# JDM2_2-Voltage_JmpConf_VDDctrl_LED.net
KiCad netlist of a schematic drawn in EAGLE
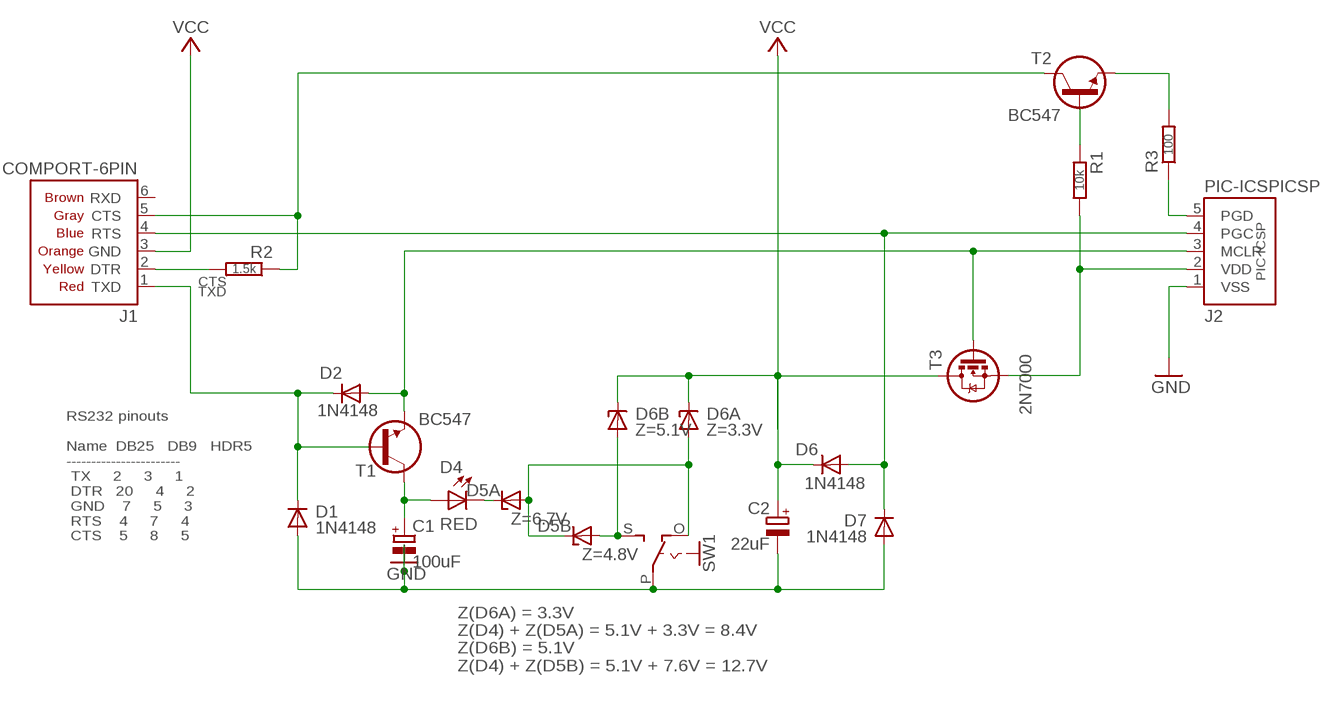
[diagram p0: schematic, sheet 1]

(export (version "E")
  (design (tool "Eeschema 10.0.6"))
  (components
    (comp (ref "C1")
      (value "100uF")
      (footprint "eagle-import:E2,5-5_V")
      (libsource (lib "eagle-import") (part "CPOLE2,5-5/V"))
    )
    (comp (ref "C2")
      (value "22uF")
      (footprint "eagle-import:E2.5-4_V")
      (libsource (lib "eagle-import") (part "CPOLE2,5-4/V"))
    )
    (comp (ref "D1")
      (value "1N4148")
      (footprint "eagle-import:DO34-5")
      (libsource (lib "eagle-import") (part "1N414834-5"))
    )
    (comp (ref "D2")
      (value "1N4148")
      (footprint "eagle-import:DO34-5")
      (libsource (lib "eagle-import") (part "1N414834-5"))
    )
    (comp (ref "D4")
      (value "RED")
      (footprint "eagle-import:LED3MM")
      (fields (field (name "MF") "VISHAY SEMICONDUCTOR"))
      (libsource (lib "eagle-import") (part "TLLR4400"))
    )
    (comp (ref "D5A")
      (value "Z=6.7V")
      (footprint "eagle-import:DO34Z7")
      (libsource (lib "eagle-import") (part "Z-DIODE34Z7"))
    )
    (comp (ref "D5B")
      (value "Z=4.8V")
      (footprint "eagle-import:DO34Z7")
      (libsource (lib "eagle-import") (part "Z-DIODE34Z7"))
    )
    (comp (ref "D6")
      (value "1N4148")
      (footprint "eagle-import:DO34-10V")
      (libsource (lib "eagle-import") (part "1N414834-10V"))
    )
    (comp (ref "D6A")
      (value "Z=3.3V")
      (footprint "eagle-import:DO34Z7V")
      (libsource (lib "eagle-import") (part "Z-DIODE34Z7V"))
    )
    (comp (ref "D6B")
      (value "Z=5.1V")
      (footprint "eagle-import:DO34Z7V")
      (libsource (lib "eagle-import") (part "Z-DIODE34Z7V"))
    )
    (comp (ref "D7")
      (value "1N4148")
      (footprint "eagle-import:DO34-7V")
      (libsource (lib "eagle-import") (part "1N414834-7V"))
    )
    (comp (ref "J1")
      (value "COMPORT-6PIN")
      (footprint "eagle-import:RS232-6PIN")
      (libsource (lib "eagle-import") (part "COMPORT-6PIN"))
    )
    (comp (ref "J2")
      (value "PIC-ICSPICSP")
      (footprint "eagle-import:PIC-ICSP")
      (libsource (lib "eagle-import") (part "PIC-ICSPICSP"))
    )
    (comp (ref "R1")
      (value "10k")
      (footprint "eagle-import:0202_7-V")
      (libsource (lib "eagle-import") (part "R0202/7-V"))
    )
    (comp (ref "R2")
      (value "1.5k")
      (footprint "eagle-import:0202_7-V")
      (libsource (lib "eagle-import") (part "R0202/7-V"))
    )
    (comp (ref "R3")
      (value "100")
      (footprint "eagle-import:0202_7")
      (libsource (lib "eagle-import") (part "R0202/7"))
    )
    (comp (ref "SW1")
      (value "SL-SW-1P-2T-JPSW")
      (footprint "eagle-import:JPSW-1P2T")
      (libsource (lib "eagle-import") (part "SL-SW-1P-2T-JPSW"))
    )
    (comp (ref "T1")
      (value "BC547")
      (footprint "eagle-import:TO92-CBE")
      (libsource (lib "eagle-import") (part "BC547CBE"))
    )
    (comp (ref "T2")
      (value "BC547")
      (footprint "eagle-import:TO92-CBE")
      (libsource (lib "eagle-import") (part "BC547CBE"))
    )
    (comp (ref "T3")
      (value "2N7000")
      (footprint "eagle-import:TO92")
      (libsource (lib "eagle-import") (part "2N7000"))
    )
  )
  (nets
    (net (code "1") (name "/CTS") (class "Default")
      (node (ref "J1") (pin "5") (pinfunction "CTS_5") (pintype "passive"))
      (node (ref "R2") (pin "1") (pinfunction "1_1") (pintype "passive"))
      (node (ref "T2") (pin "C") (pinfunction "C_C") (pintype "passive"))
    )
    (net (code "2") (name "/TXD") (class "Default")
      (node (ref "D1") (pin "C") (pinfunction "C_C") (pintype "passive"))
      (node (ref "D2") (pin "C") (pinfunction "C_C") (pintype "passive"))
      (node (ref "J1") (pin "1") (pinfunction "TXD_1") (pintype "passive"))
      (node (ref "T1") (pin "B") (pinfunction "B_B") (pintype "passive"))
    )
    (net (code "3") (name "GND") (class "Default")
      (node (ref "C1") (pin "-") (pinfunction "-_-") (pintype "passive"))
      (node (ref "C2") (pin "-") (pinfunction "-_-") (pintype "passive"))
      (node (ref "D1") (pin "A") (pinfunction "A_A") (pintype "passive"))
      (node (ref "D7") (pin "A") (pinfunction "A_A") (pintype "passive"))
      (node (ref "J2") (pin "1") (pinfunction "VSS_1") (pintype "passive"))
      (node (ref "SW1") (pin "P") (pinfunction "P_P") (pintype "passive"))
    )
    (net (code "4") (name "Net-(C1-Pad+)") (class "Default")
      (node (ref "C1") (pin "+") (pinfunction "+_+") (pintype "passive"))
      (node (ref "D4") (pin "A") (pinfunction "A_A") (pintype "passive"))
      (node (ref "T1") (pin "C") (pinfunction "C_C") (pintype "passive"))
    )
    (net (code "5") (name "Net-(D4-C)") (class "Default")
      (node (ref "D4") (pin "K") (pinfunction "C_K") (pintype "passive"))
      (node (ref "D5A") (pin "C") (pinfunction "C_C") (pintype "passive"))
    )
    (net (code "6") (name "Net-(D5A-PadA)") (class "Default")
      (node (ref "D5A") (pin "A") (pinfunction "A_A") (pintype "passive"))
      (node (ref "D5B") (pin "C") (pinfunction "C_C") (pintype "passive"))
      (node (ref "D6A") (pin "A") (pinfunction "A_A") (pintype "passive"))
      (node (ref "SW1") (pin "O") (pinfunction "O_O") (pintype "passive"))
    )
    (net (code "7") (name "Net-(D5B-PadA)") (class "Default")
      (node (ref "D5B") (pin "A") (pinfunction "A_A") (pintype "passive"))
      (node (ref "D6B") (pin "A") (pinfunction "A_A") (pintype "passive"))
      (node (ref "SW1") (pin "S") (pinfunction "S_S") (pintype "passive"))
    )
    (net (code "8") (name "Net-(J1-DTR)") (class "Default")
      (node (ref "J1") (pin "2") (pinfunction "DTR_2") (pintype "passive"))
      (node (ref "R2") (pin "2") (pinfunction "2_2") (pintype "passive"))
    )
    (net (code "9") (name "Net-(J1-RTS)") (class "Default")
      (node (ref "D6") (pin "A") (pinfunction "A_A") (pintype "passive"))
      (node (ref "D7") (pin "C") (pinfunction "C_C") (pintype "passive"))
      (node (ref "J1") (pin "4") (pinfunction "RTS_4") (pintype "passive"))
      (node (ref "J2") (pin "4") (pinfunction "PGC_4") (pintype "passive"))
    )
    (net (code "10") (name "Net-(J2-MCLR)") (class "Default")
      (node (ref "D2") (pin "A") (pinfunction "A_A") (pintype "passive"))
      (node (ref "J2") (pin "3") (pinfunction "MCLR_3") (pintype "passive"))
      (node (ref "T1") (pin "E") (pinfunction "E_E") (pintype "passive"))
      (node (ref "T3") (pin "2") (pinfunction "G_2") (pintype "passive"))
    )
    (net (code "11") (name "Net-(J2-PGD)") (class "Default")
      (node (ref "J2") (pin "5") (pinfunction "PGD_5") (pintype "passive"))
      (node (ref "R3") (pin "1") (pinfunction "1_1") (pintype "passive"))
    )
    (net (code "12") (name "Net-(J2-VDD)") (class "Default")
      (node (ref "J2") (pin "2") (pinfunction "VDD_2") (pintype "passive"))
      (node (ref "R1") (pin "2") (pinfunction "2_2") (pintype "passive"))
      (node (ref "T3") (pin "1") (pinfunction "S_1") (pintype "passive"))
    )
    (net (code "13") (name "Net-(R1-Pad1)") (class "Default")
      (node (ref "R1") (pin "1") (pinfunction "1_1") (pintype "passive"))
      (node (ref "T2") (pin "B") (pinfunction "B_B") (pintype "passive"))
    )
    (net (code "14") (name "Net-(R3-Pad2)") (class "Default")
      (node (ref "R3") (pin "2") (pinfunction "2_2") (pintype "passive"))
      (node (ref "T2") (pin "E") (pinfunction "E_E") (pintype "passive"))
    )
    (net (code "15") (name "VCC") (class "Default")
      (node (ref "C2") (pin "+") (pinfunction "+_+") (pintype "passive"))
      (node (ref "D6") (pin "C") (pinfunction "C_C") (pintype "passive"))
      (node (ref "D6A") (pin "C") (pinfunction "C_C") (pintype "passive"))
      (node (ref "D6B") (pin "C") (pinfunction "C_C") (pintype "passive"))
      (node (ref "J1") (pin "3") (pinfunction "GND_3") (pintype "passive"))
      (node (ref "T3") (pin "3") (pinfunction "D_3") (pintype "passive"))
    )
    (net (code "16") (name "unconnected-(J1-RXD-Pad6)") (class "Default")
      (node (ref "J1") (pin "6") (pinfunction "RXD_6") (pintype "passive"))
    )
  )
)
